# LB_o3_RGB_LED-v03_rev2.net
KiCad netlist of a schematic drawn in EAGLE
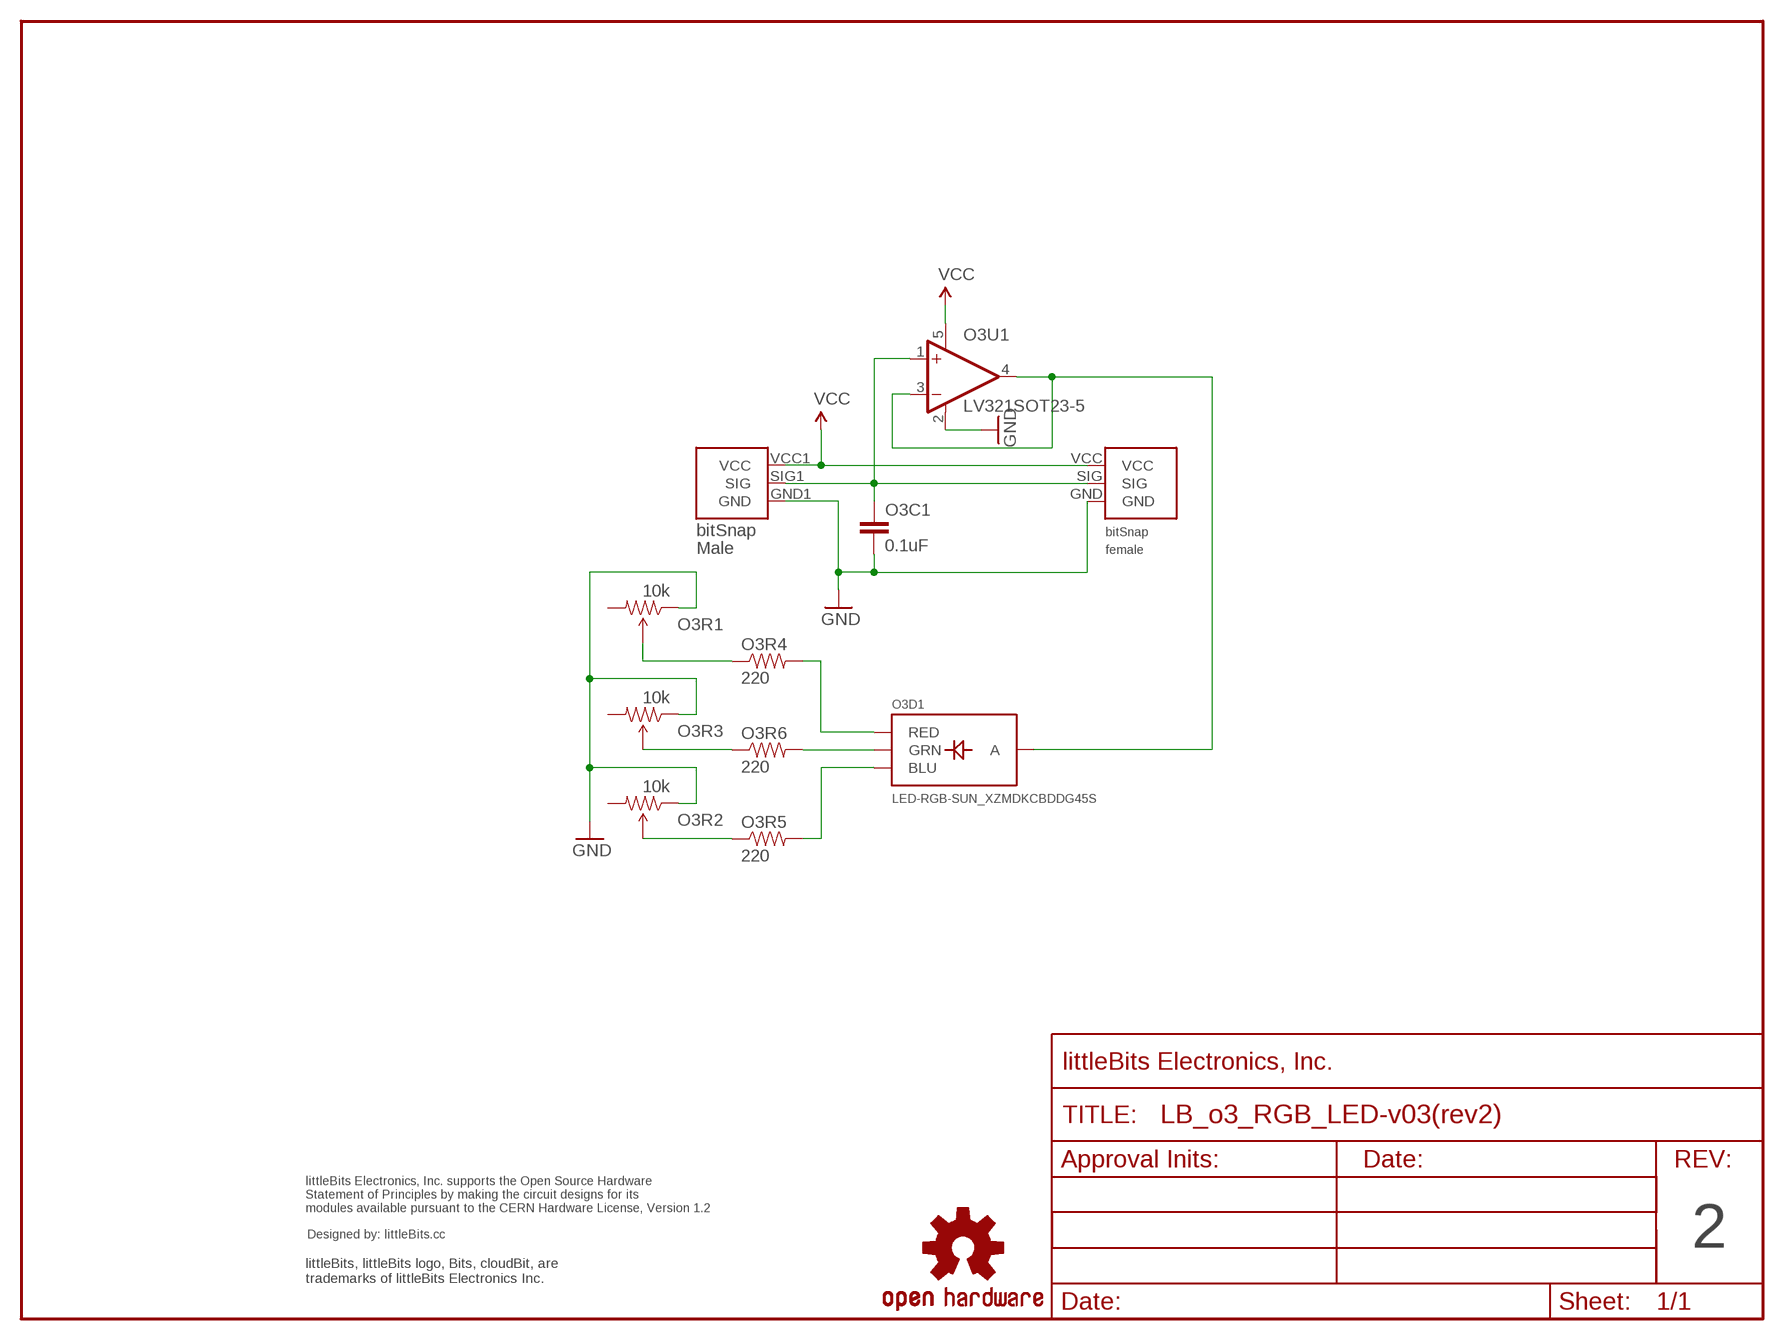
[diagram p0: schematic, sheet 1]

(export (version "E")
  (design (tool "Eeschema 10.0.6"))
  (components
    (comp (ref "O3BSF1")
      (value "BITSNAP_V03_FEMALE")
      (footprint "eagle-import:BITSNAP_V03_FEMALE")
      (libsource (lib "eagle-import") (part "BITSNAP_V03_FEMALE"))
    )
    (comp (ref "O3BSM1")
      (value "BITSNAP_V03_MALE")
      (footprint "eagle-import:BITSNAP_V03_MALE")
      (libsource (lib "eagle-import") (part "BITSNAP_V03_MALE"))
    )
    (comp (ref "O3C1")
      (value "0.1uF")
      (footprint "eagle-import:0603-CAP")
      (libsource (lib "eagle-import") (part "CAP0603-CAP"))
    )
    (comp (ref "O3D1")
      (value "LED-RGB-SUN_XZMDKCBDDG45S")
      (footprint "eagle-import:LED-RGB-SUN_XZMDKCBDDG45S")
      (libsource (lib "eagle-import") (part "LED-RGB-SUN_XZMDKCBDDG45S"))
    )
    (comp (ref "O3R1")
      (value "10k")
      (footprint "eagle-import:TRIMPOT-3MM")
      (libsource (lib "eagle-import") (part "TRIMPOTSMD"))
    )
    (comp (ref "O3R2")
      (value "10k")
      (footprint "eagle-import:TRIMPOT-3MM")
      (libsource (lib "eagle-import") (part "TRIMPOTSMD"))
    )
    (comp (ref "O3R3")
      (value "10k")
      (footprint "eagle-import:TRIMPOT-3MM")
      (libsource (lib "eagle-import") (part "TRIMPOTSMD"))
    )
    (comp (ref "O3R4")
      (value "220")
      (footprint "eagle-import:0603-RES")
      (libsource (lib "eagle-import") (part "RESISTOR0603-RES"))
    )
    (comp (ref "O3R5")
      (value "220")
      (footprint "eagle-import:0603-RES")
      (libsource (lib "eagle-import") (part "RESISTOR0603-RES"))
    )
    (comp (ref "O3R6")
      (value "220")
      (footprint "eagle-import:0603-RES")
      (libsource (lib "eagle-import") (part "RESISTOR0603-RES"))
    )
    (comp (ref "O3U1")
      (value "LV321SOT23-5")
      (footprint "eagle-import:SOT23-5")
      (libsource (lib "eagle-import") (part "LV321SOT23-5"))
    )
    (comp (ref "U$1")
      (value "FRAME-LETTER-OHWOHW")
      (footprint "eagle-import:FABDWG01-OHW")
      (libsource (lib "eagle-import") (part "FRAME-LETTER-OHWOHW"))
    )
    (comp (ref "U$2")
      (value "OSHWCREDIT")
      (footprint "eagle-import:OSHWCREDIT")
      (libsource (lib "eagle-import") (part "OSHWCREDIT"))
    )
    (comp (ref "U$5")
      (value "OSHW-LOGOL")
      (footprint "eagle-import:OSHW-LOGO-L")
      (libsource (lib "eagle-import") (part "OSHW-LOGOL"))
    )
  )
  (nets
    (net (code "1") (name "GND") (class "Default")
      (node (ref "O3BSF1") (pin "GND") (pinfunction "GND_GND") (pintype "bidirectional"))
      (node (ref "O3BSM1") (pin "GND1") (pinfunction "GND_GND1") (pintype "bidirectional"))
      (node (ref "O3C1") (pin "2") (pinfunction "2_2") (pintype "passive"))
      (node (ref "O3R1") (pin "1") (pinfunction "CCW_1") (pintype "passive"))
      (node (ref "O3R2") (pin "1") (pinfunction "CCW_1") (pintype "passive"))
      (node (ref "O3R3") (pin "1") (pinfunction "CCW_1") (pintype "passive"))
      (node (ref "O3U1") (pin "2") (pinfunction "V-_2") (pintype "power_in"))
    )
    (net (code "2") (name "Net-(O3BSM1-SIG)") (class "Default")
      (node (ref "O3BSF1") (pin "SIG") (pinfunction "SIG_SIG") (pintype "bidirectional"))
      (node (ref "O3BSM1") (pin "SIG1") (pinfunction "SIG_SIG1") (pintype "bidirectional"))
      (node (ref "O3C1") (pin "1") (pinfunction "1_1") (pintype "passive"))
      (node (ref "O3U1") (pin "1") (pinfunction "+IN_1") (pintype "input"))
    )
    (net (code "3") (name "Net-(O3D1-A)") (class "Default")
      (node (ref "O3D1") (pin "2") (pinfunction "A_2") (pintype "bidirectional"))
      (node (ref "O3U1") (pin "3") (pinfunction "-IN_3") (pintype "input"))
      (node (ref "O3U1") (pin "4") (pinfunction "OUT_4") (pintype "output"))
    )
    (net (code "4") (name "Net-(O3D1-BLU)") (class "Default")
      (node (ref "O3D1") (pin "3") (pinfunction "BLU_3") (pintype "bidirectional"))
      (node (ref "O3R5") (pin "2") (pinfunction "2_2") (pintype "passive"))
    )
    (net (code "5") (name "Net-(O3D1-GRN)") (class "Default")
      (node (ref "O3D1") (pin "4") (pinfunction "GRN_4") (pintype "bidirectional"))
      (node (ref "O3R6") (pin "2") (pinfunction "2_2") (pintype "passive"))
    )
    (net (code "6") (name "Net-(O3D1-RED)") (class "Default")
      (node (ref "O3D1") (pin "1") (pinfunction "RED_1") (pintype "bidirectional"))
      (node (ref "O3R4") (pin "2") (pinfunction "2_2") (pintype "passive"))
    )
    (net (code "7") (name "Net-(O3R1-WIPER)") (class "Default")
      (node (ref "O3R1") (pin "2") (pinfunction "WIPER_2") (pintype "passive"))
      (node (ref "O3R4") (pin "1") (pinfunction "1_1") (pintype "passive"))
    )
    (net (code "8") (name "Net-(O3R2-WIPER)") (class "Default")
      (node (ref "O3R2") (pin "2") (pinfunction "WIPER_2") (pintype "passive"))
      (node (ref "O3R5") (pin "1") (pinfunction "1_1") (pintype "passive"))
    )
    (net (code "9") (name "Net-(O3R3-WIPER)") (class "Default")
      (node (ref "O3R3") (pin "2") (pinfunction "WIPER_2") (pintype "passive"))
      (node (ref "O3R6") (pin "1") (pinfunction "1_1") (pintype "passive"))
    )
    (net (code "10") (name "VCC") (class "Default")
      (node (ref "O3BSF1") (pin "VCC") (pinfunction "VCC_VCC") (pintype "bidirectional"))
      (node (ref "O3BSM1") (pin "VCC1") (pinfunction "VCC_VCC1") (pintype "bidirectional"))
      (node (ref "O3U1") (pin "5") (pinfunction "V+_5") (pintype "power_in"))
    )
    (net (code "11") (name "unconnected-(O3R1-CW-Pad3)") (class "Default")
      (node (ref "O3R1") (pin "3") (pinfunction "CW_3") (pintype "passive"))
    )
    (net (code "12") (name "unconnected-(O3R2-CW-Pad3)") (class "Default")
      (node (ref "O3R2") (pin "3") (pinfunction "CW_3") (pintype "passive"))
    )
    (net (code "13") (name "unconnected-(O3R3-CW-Pad3)") (class "Default")
      (node (ref "O3R3") (pin "3") (pinfunction "CW_3") (pintype "passive"))
    )
  )
)
